# QuadADSR.net
KiCad netlist of a schematic drawn in EAGLE
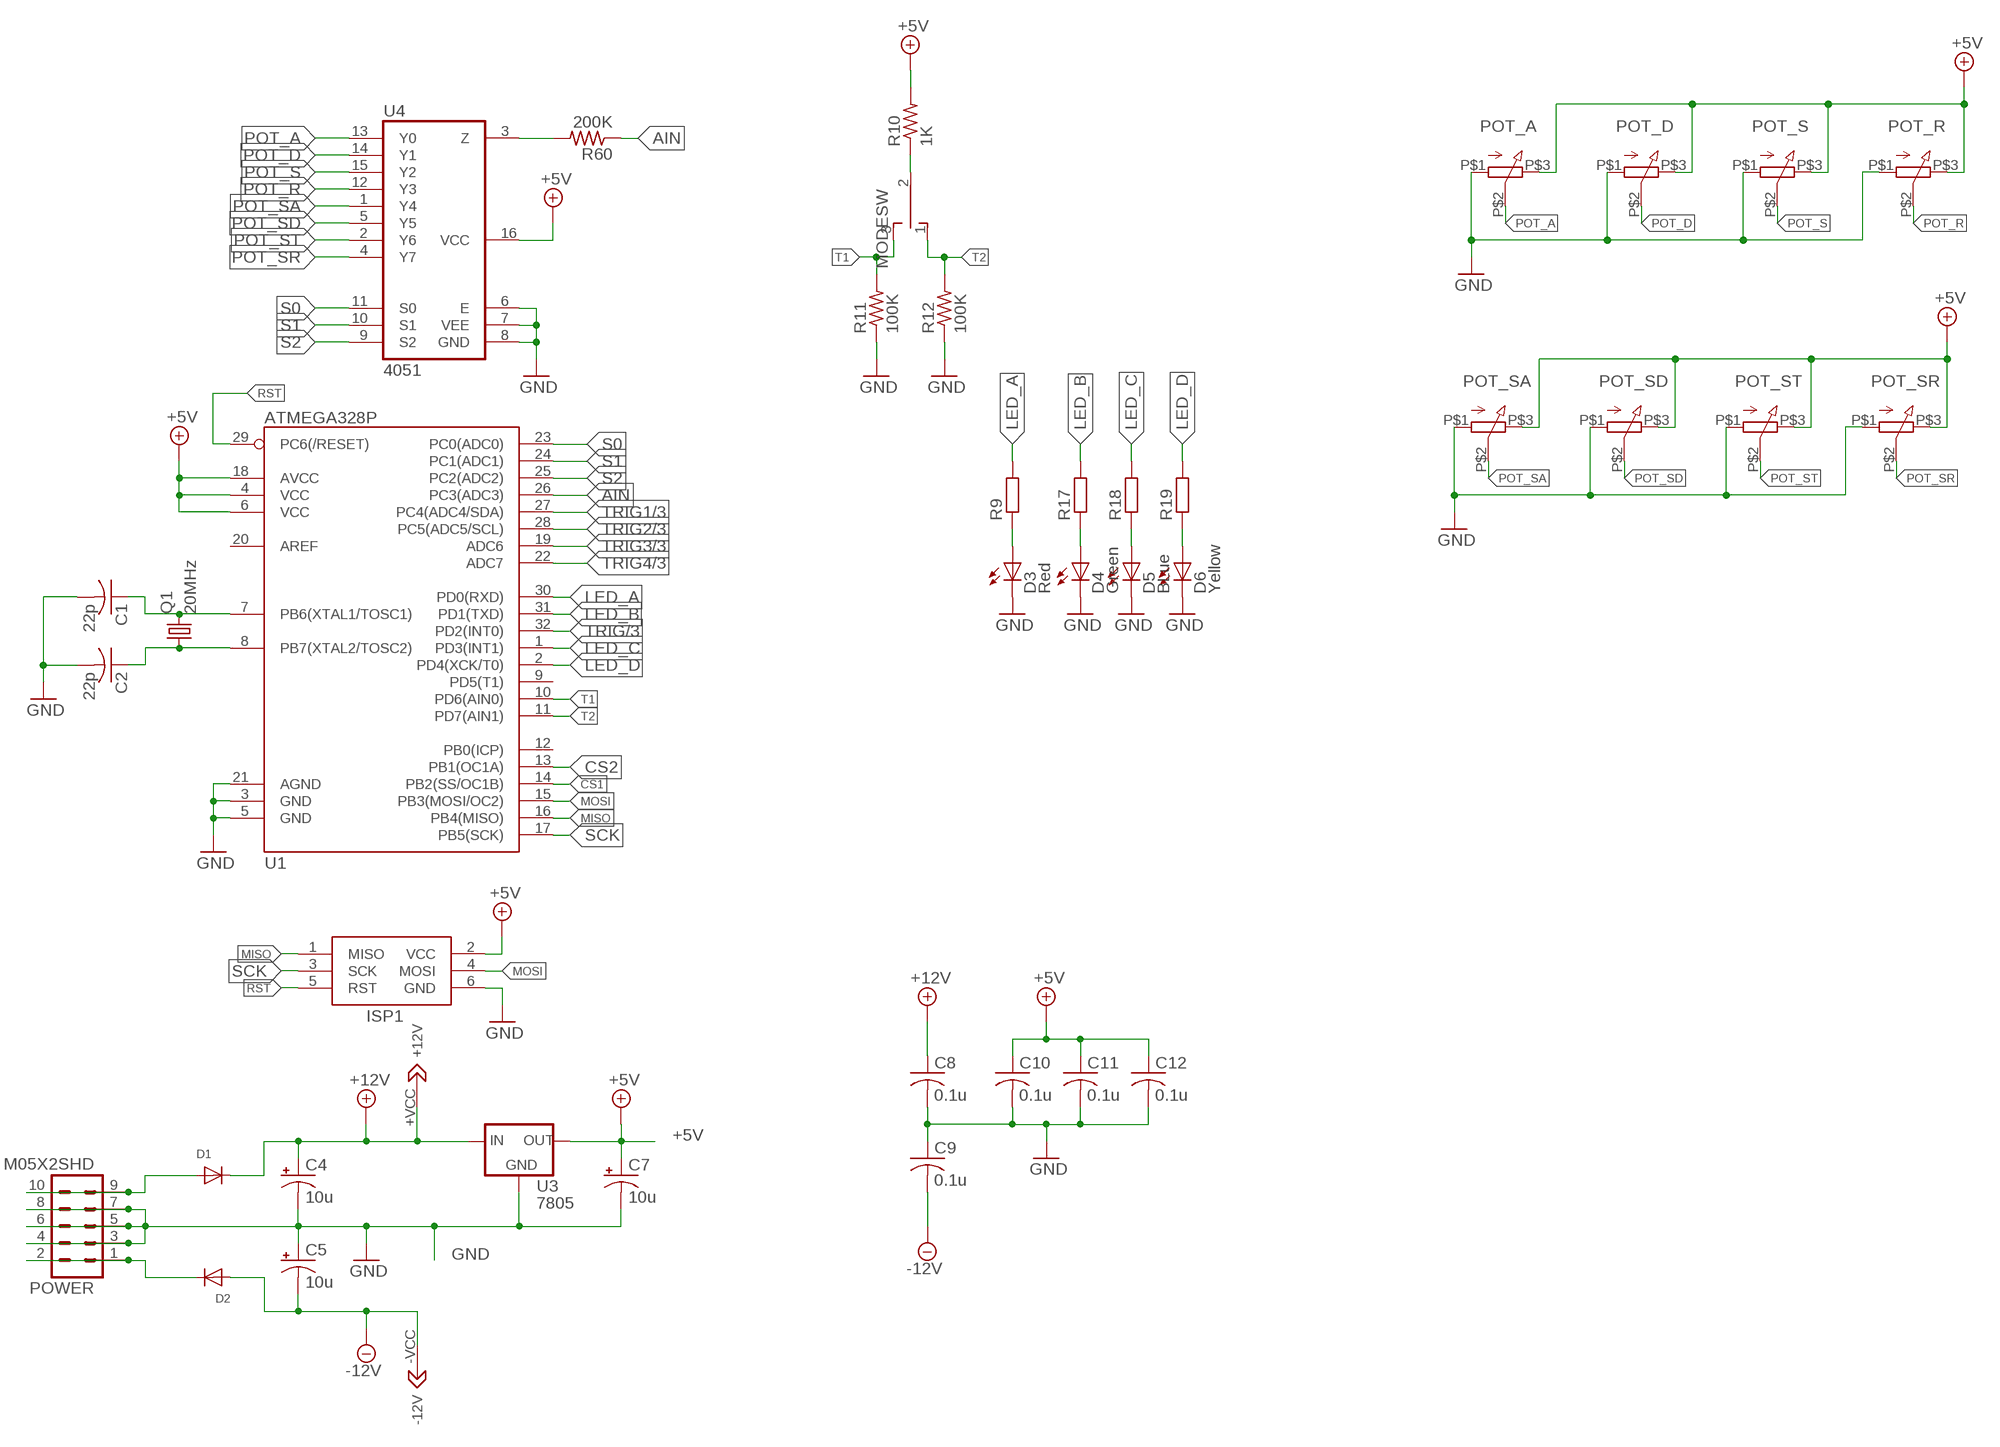
[diagram p0: schematic, sheet 1]
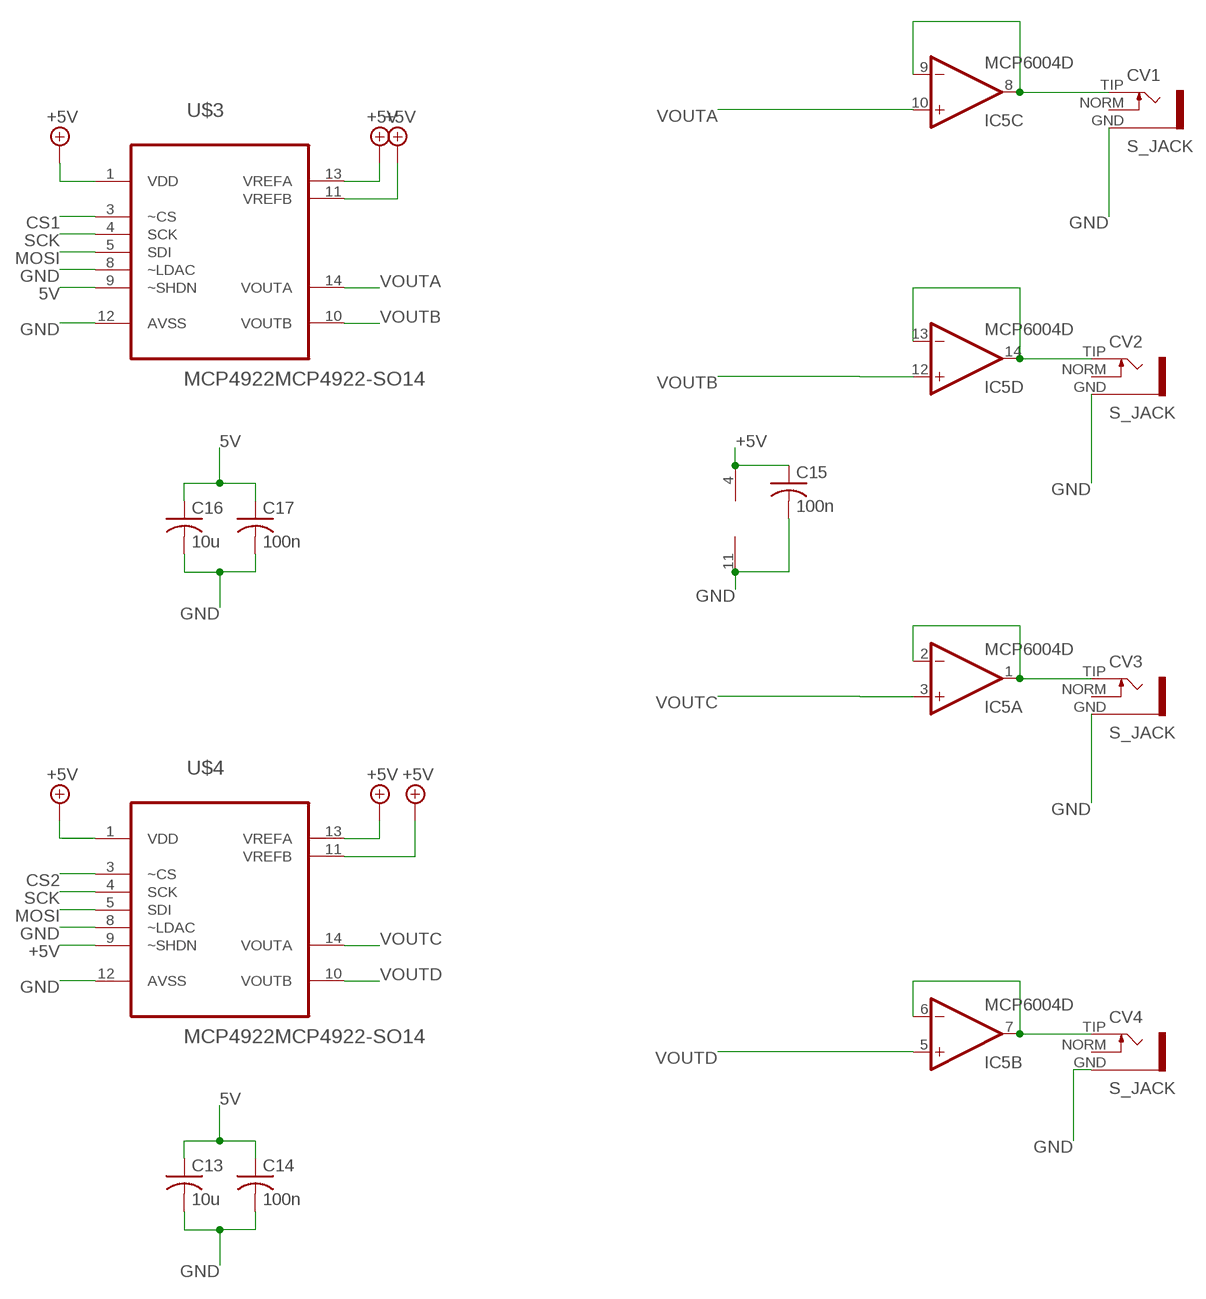
[diagram p1: schematic, sheet 2]
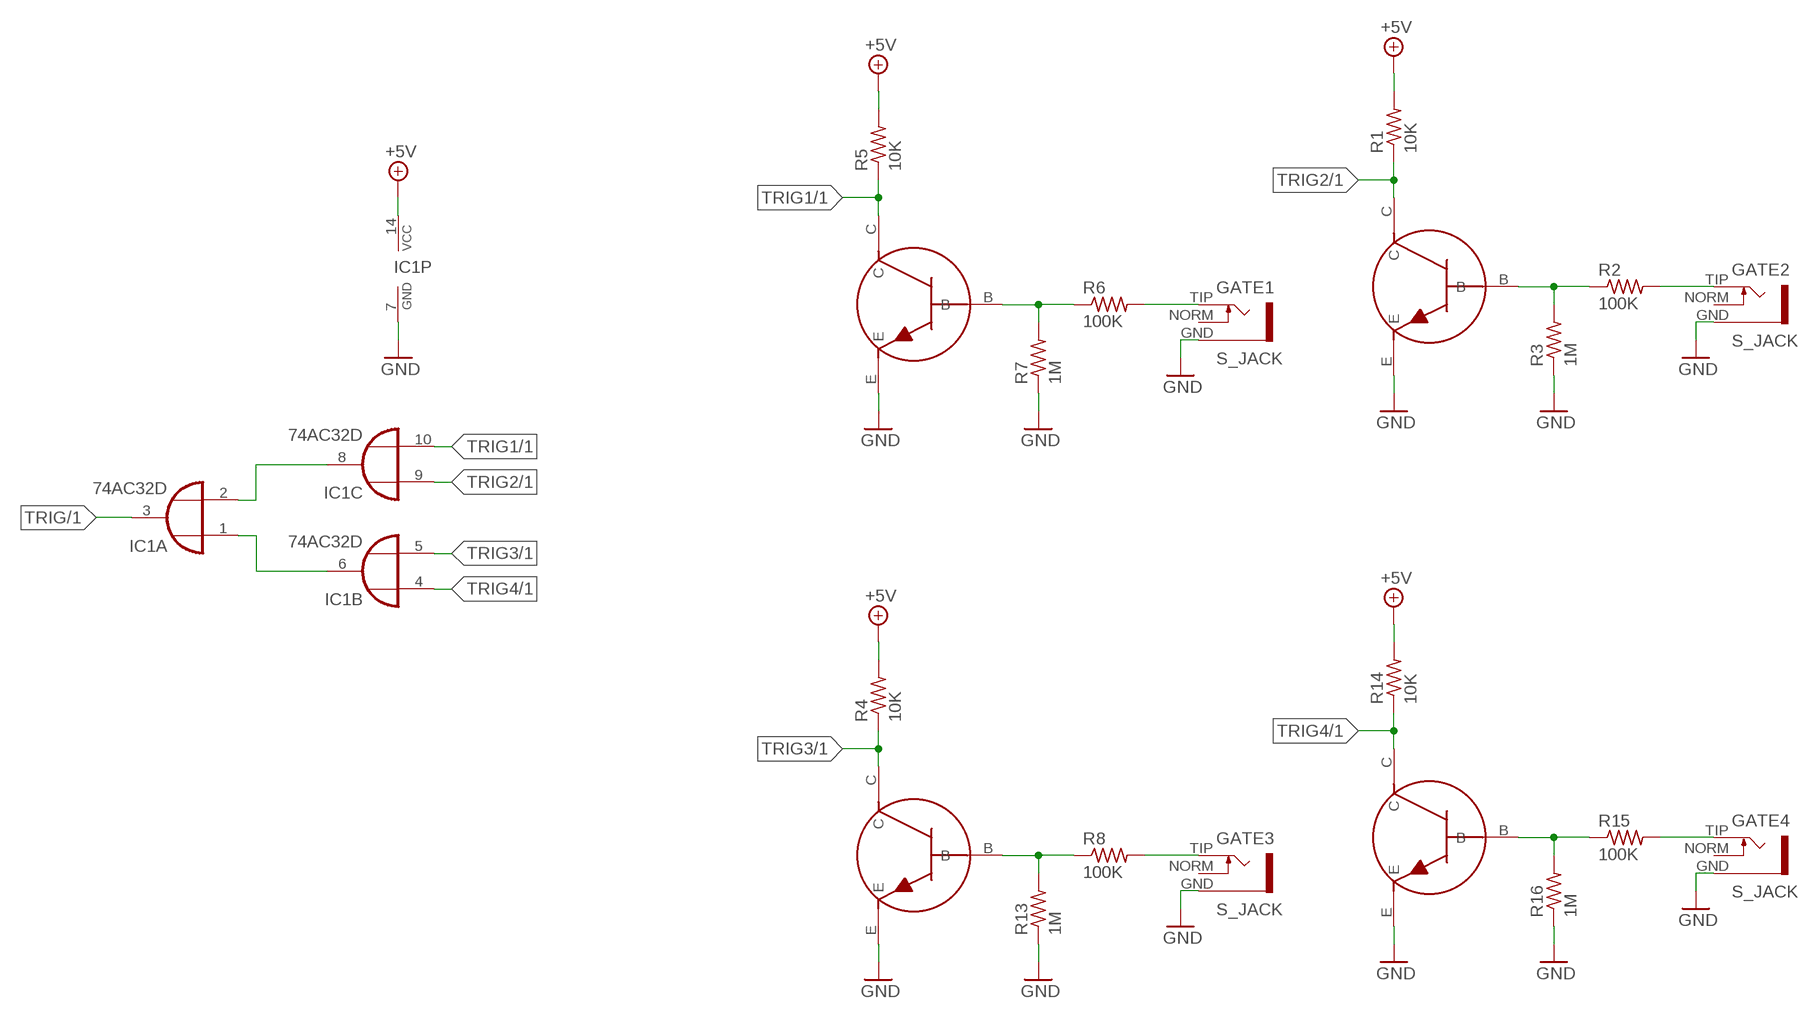
[diagram p2: schematic, sheet 3]

(export (version "E")
  (design (tool "Eeschema 10.0.6"))
  (components
    (comp (ref "C1")
      (value "22p")
      (footprint "eagle-import:C0805K")
      (libsource (lib "eagle-import") (part "C-USC0805K"))
    )
    (comp (ref "C2")
      (value "22p")
      (footprint "eagle-import:C0805K")
      (libsource (lib "eagle-import") (part "C-USC0805K"))
    )
    (comp (ref "C4")
      (value "10u")
      (footprint "eagle-import:153CLV-0505")
      (libsource (lib "eagle-import") (part "CPOL-US153CLV-0505"))
    )
    (comp (ref "C5")
      (value "10u")
      (footprint "eagle-import:153CLV-0505")
      (libsource (lib "eagle-import") (part "CPOL-US153CLV-0505"))
    )
    (comp (ref "C7")
      (value "10u")
      (footprint "eagle-import:153CLV-0505")
      (libsource (lib "eagle-import") (part "CPOL-US153CLV-0505"))
    )
    (comp (ref "C8")
      (value "0.1u")
      (footprint "eagle-import:C0805K")
      (libsource (lib "eagle-import") (part "C-USC0805K"))
    )
    (comp (ref "C9")
      (value "0.1u")
      (footprint "eagle-import:C0805K")
      (libsource (lib "eagle-import") (part "C-USC0805K"))
    )
    (comp (ref "C10")
      (value "0.1u")
      (footprint "eagle-import:C0805K")
      (libsource (lib "eagle-import") (part "C-USC0805K"))
    )
    (comp (ref "C11")
      (value "0.1u")
      (footprint "eagle-import:C0805K")
      (libsource (lib "eagle-import") (part "C-USC0805K"))
    )
    (comp (ref "C12")
      (value "0.1u")
      (footprint "eagle-import:C0805K")
      (libsource (lib "eagle-import") (part "C-USC0805K"))
    )
    (comp (ref "D1")
      (value "DIODESMA")
      (footprint "eagle-import:SMADIODE")
      (libsource (lib "eagle-import") (part "DIODESMA"))
    )
    (comp (ref "D2")
      (value "DIODESMA")
      (footprint "eagle-import:SMADIODE")
      (libsource (lib "eagle-import") (part "DIODESMA"))
    )
    (comp (ref "D3")
      (value "Red")
      (footprint "eagle-import:LED5MM")
      (libsource (lib "eagle-import") (part "LED5MM"))
    )
    (comp (ref "D4")
      (value "Green")
      (footprint "eagle-import:LED5MM")
      (libsource (lib "eagle-import") (part "LED5MM"))
    )
    (comp (ref "D5")
      (value "BLue")
      (footprint "eagle-import:LED5MM")
      (libsource (lib "eagle-import") (part "LED5MM"))
    )
    (comp (ref "D6")
      (value "Yellow")
      (footprint "eagle-import:LED5MM")
      (libsource (lib "eagle-import") (part "LED5MM"))
    )
    (comp (ref "ISP1")
      (value "AVRISP-6")
      (footprint "eagle-import:AVRISP")
      (libsource (lib "eagle-import") (part "AVRISP-6"))
    )
    (comp (ref "MODESW")
      (value "TOGGLE_ON_OFF_ON")
      (footprint "eagle-import:TOGGLE_ON_OFF_ON")
      (libsource (lib "eagle-import") (part "TOGGLE_ON_OFF_ON"))
    )
    (comp (ref "POT_A")
      (value "Q-POT")
      (footprint "eagle-import:Q-POT")
      (libsource (lib "eagle-import") (part "Q-POT"))
    )
    (comp (ref "POT_D")
      (value "Q-POT")
      (footprint "eagle-import:Q-POT")
      (libsource (lib "eagle-import") (part "Q-POT"))
    )
    (comp (ref "POT_R")
      (value "Q-POT")
      (footprint "eagle-import:Q-POT")
      (libsource (lib "eagle-import") (part "Q-POT"))
    )
    (comp (ref "POT_S")
      (value "Q-POT")
      (footprint "eagle-import:Q-POT")
      (libsource (lib "eagle-import") (part "Q-POT"))
    )
    (comp (ref "POT_SA")
      (value "Q-POT")
      (footprint "eagle-import:Q-POT")
      (libsource (lib "eagle-import") (part "Q-POT"))
    )
    (comp (ref "POT_SD")
      (value "Q-POT")
      (footprint "eagle-import:Q-POT")
      (libsource (lib "eagle-import") (part "Q-POT"))
    )
    (comp (ref "POT_SR")
      (value "Q-POT")
      (footprint "eagle-import:Q-POT")
      (libsource (lib "eagle-import") (part "Q-POT"))
    )
    (comp (ref "POT_ST")
      (value "Q-POT")
      (footprint "eagle-import:Q-POT")
      (libsource (lib "eagle-import") (part "Q-POT"))
    )
    (comp (ref "POWER")
      (value "M05X2SHD")
      (footprint "eagle-import:2X5-SHROUDED")
      (libsource (lib "eagle-import") (part "M05X2SHD"))
    )
    (comp (ref "Q1")
      (value "20MHz")
      (footprint "eagle-import:HC49UP")
      (libsource (lib "eagle-import") (part "CRYSTALHC49UP"))
    )
    (comp (ref "R9")
      (value "R-EU_R0805")
      (footprint "eagle-import:R0805")
      (libsource (lib "eagle-import") (part "R-EU_R0805"))
    )
    (comp (ref "R10")
      (value "1K")
      (footprint "eagle-import:R0805")
      (libsource (lib "eagle-import") (part "rcl_334_R-US_R0805"))
    )
    (comp (ref "R11")
      (value "100K")
      (footprint "eagle-import:R0805")
      (libsource (lib "eagle-import") (part "rcl_334_R-US_R0805"))
    )
    (comp (ref "R12")
      (value "100K")
      (footprint "eagle-import:R0805")
      (libsource (lib "eagle-import") (part "rcl_334_R-US_R0805"))
    )
    (comp (ref "R17")
      (value "R-EU_R0805")
      (footprint "eagle-import:R0805")
      (libsource (lib "eagle-import") (part "R-EU_R0805"))
    )
    (comp (ref "R18")
      (value "R-EU_R0805")
      (footprint "eagle-import:R0805")
      (libsource (lib "eagle-import") (part "R-EU_R0805"))
    )
    (comp (ref "R19")
      (value "R-EU_R0805")
      (footprint "eagle-import:R0805")
      (libsource (lib "eagle-import") (part "R-EU_R0805"))
    )
    (comp (ref "R60")
      (value "200K")
      (footprint "eagle-import:R0805")
      (libsource (lib "eagle-import") (part "R-US_R0805"))
    )
    (comp (ref "U1")
      (value "ATMEGA328P")
      (footprint "eagle-import:TQFP32-08")
      (libsource (lib "eagle-import") (part "ATMEGA328_SMT"))
    )
    (comp (ref "U2")
      (value "DUAL_OPAMP")
      (footprint "eagle-import:DUAL_OPAMP")
      (libsource (lib "eagle-import") (part "DUAL_OPAMP"))
    )
    (comp (ref "U3")
      (value "7805")
      (footprint "eagle-import:V-REG")
      (libsource (lib "eagle-import") (part "V-REG"))
    )
    (comp (ref "U4")
      (value "4051")
      (footprint "eagle-import:N2222_ARRAY")
      (libsource (lib "eagle-import") (part "MUX!"))
    )
    (comp (ref "GATE1")
      (value "S_JACK")
      (footprint "eagle-import:S_JACK")
      (libsource (lib "eagle-import") (part "S_JACK"))
    )
    (comp (ref "GATE2")
      (value "S_JACK")
      (footprint "eagle-import:S_JACK")
      (libsource (lib "eagle-import") (part "S_JACK"))
    )
    (comp (ref "GATE3")
      (value "S_JACK")
      (footprint "eagle-import:S_JACK")
      (libsource (lib "eagle-import") (part "S_JACK"))
    )
    (comp (ref "GATE4")
      (value "S_JACK")
      (footprint "eagle-import:S_JACK")
      (libsource (lib "eagle-import") (part "S_JACK"))
    )
    (comp (ref "IC1")
      (value "74AC32D")
      (footprint "eagle-import:SO14")
      (libsource (lib "eagle-import") (part "7432DAC"))
    )
    (comp (ref "R1")
      (value "10K")
      (footprint "eagle-import:R0805")
      (libsource (lib "eagle-import") (part "rcl_334_R-US_R0805"))
    )
    (comp (ref "R2")
      (value "100K")
      (footprint "eagle-import:R0805")
      (libsource (lib "eagle-import") (part "rcl_334_R-US_R0805"))
    )
    (comp (ref "R3")
      (value "1M")
      (footprint "eagle-import:R0805")
      (libsource (lib "eagle-import") (part "rcl_334_R-US_R0805"))
    )
    (comp (ref "R4")
      (value "10K")
      (footprint "eagle-import:R0805")
      (libsource (lib "eagle-import") (part "rcl_334_R-US_R0805"))
    )
    (comp (ref "R5")
      (value "10K")
      (footprint "eagle-import:R0805")
      (libsource (lib "eagle-import") (part "rcl_334_R-US_R0805"))
    )
    (comp (ref "R6")
      (value "100K")
      (footprint "eagle-import:R0805")
      (libsource (lib "eagle-import") (part "rcl_334_R-US_R0805"))
    )
    (comp (ref "R7")
      (value "1M")
      (footprint "eagle-import:R0805")
      (libsource (lib "eagle-import") (part "rcl_334_R-US_R0805"))
    )
    (comp (ref "R8")
      (value "100K")
      (footprint "eagle-import:R0805")
      (libsource (lib "eagle-import") (part "rcl_334_R-US_R0805"))
    )
    (comp (ref "R13")
      (value "1M")
      (footprint "eagle-import:R0805")
      (libsource (lib "eagle-import") (part "rcl_334_R-US_R0805"))
    )
    (comp (ref "R14")
      (value "10K")
      (footprint "eagle-import:R0805")
      (libsource (lib "eagle-import") (part "rcl_334_R-US_R0805"))
    )
    (comp (ref "R15")
      (value "100K")
      (footprint "eagle-import:R0805")
      (libsource (lib "eagle-import") (part "rcl_334_R-US_R0805"))
    )
    (comp (ref "R16")
      (value "1M")
      (footprint "eagle-import:R0805")
      (libsource (lib "eagle-import") (part "rcl_334_R-US_R0805"))
    )
    (comp (ref "T1")
      (value "2N3904")
      (footprint "eagle-import:TRANSISTOR_SINGLE_N-TYPE")
      (libsource (lib "eagle-import") (part "TRANSISTOR_MMBT3904"))
    )
    (comp (ref "T2")
      (value "2N3904")
      (footprint "eagle-import:TRANSISTOR_SINGLE_N-TYPE")
      (libsource (lib "eagle-import") (part "TRANSISTOR_MMBT3904"))
    )
    (comp (ref "T3")
      (value "2N3904")
      (footprint "eagle-import:TRANSISTOR_SINGLE_N-TYPE")
      (libsource (lib "eagle-import") (part "TRANSISTOR_MMBT3904"))
    )
    (comp (ref "T4")
      (value "2N3904")
      (footprint "eagle-import:TRANSISTOR_SINGLE_N-TYPE")
      (libsource (lib "eagle-import") (part "TRANSISTOR_MMBT3904"))
    )
    (comp (ref "C13")
      (value "10u")
      (footprint "eagle-import:C0805K")
      (libsource (lib "eagle-import") (part "C-USC0805K"))
    )
    (comp (ref "C14")
      (value "100n")
      (footprint "eagle-import:C0805K")
      (libsource (lib "eagle-import") (part "C-USC0805K"))
    )
    (comp (ref "C15")
      (value "100n")
      (footprint "eagle-import:C0805K")
      (libsource (lib "eagle-import") (part "C-USC0805K"))
    )
    (comp (ref "C16")
      (value "10u")
      (footprint "eagle-import:C0805K")
      (libsource (lib "eagle-import") (part "C-USC0805K"))
    )
    (comp (ref "C17")
      (value "100n")
      (footprint "eagle-import:C0805K")
      (libsource (lib "eagle-import") (part "C-USC0805K"))
    )
    (comp (ref "CV1")
      (value "S_JACK")
      (footprint "eagle-import:S_JACK")
      (libsource (lib "eagle-import") (part "S_JACK"))
    )
    (comp (ref "CV2")
      (value "S_JACK")
      (footprint "eagle-import:S_JACK")
      (libsource (lib "eagle-import") (part "S_JACK"))
    )
    (comp (ref "CV3")
      (value "S_JACK")
      (footprint "eagle-import:S_JACK")
      (libsource (lib "eagle-import") (part "S_JACK"))
    )
    (comp (ref "CV4")
      (value "S_JACK")
      (footprint "eagle-import:S_JACK")
      (libsource (lib "eagle-import") (part "S_JACK"))
    )
    (comp (ref "IC5")
      (value "MCP6004D")
      (footprint "eagle-import:SO14")
      (libsource (lib "eagle-import") (part "MCP6004D"))
    )
    (comp (ref "U$3")
      (value "MCP4922MCP4922-SO14")
      (footprint "eagle-import:SO14")
      (libsource (lib "eagle-import") (part "MCP4922MCP4922-SO14"))
    )
    (comp (ref "U$4")
      (value "MCP4922MCP4922-SO14")
      (footprint "eagle-import:SO14")
      (libsource (lib "eagle-import") (part "MCP4922MCP4922-SO14"))
    )
  )
  (nets
    (net (code "1") (name "+5V") (class "Default")
      (node (ref "C10") (pin "1") (pinfunction "1_1") (pintype "passive"))
      (node (ref "C11") (pin "1") (pinfunction "1_1") (pintype "passive"))
      (node (ref "C12") (pin "1") (pinfunction "1_1") (pintype "passive"))
      (node (ref "C15") (pin "1") (pinfunction "1_1") (pintype "passive"))
      (node (ref "C7") (pin "+") (pinfunction "+_+") (pintype "passive"))
      (node (ref "IC1") (pin "14") (pinfunction "VCC_14") (pintype "power_in"))
      (node (ref "IC5") (pin "4") (pinfunction "V+_4") (pintype "power_in"))
      (node (ref "ISP1") (pin "2") (pinfunction "VCC_2") (pintype "power_in"))
      (node (ref "POT_A") (pin "P$3") (pinfunction "3_P$3") (pintype "passive"))
      (node (ref "POT_D") (pin "P$3") (pinfunction "3_P$3") (pintype "passive"))
      (node (ref "POT_R") (pin "P$3") (pinfunction "3_P$3") (pintype "passive"))
      (node (ref "POT_S") (pin "P$3") (pinfunction "3_P$3") (pintype "passive"))
      (node (ref "POT_SA") (pin "P$3") (pinfunction "3_P$3") (pintype "passive"))
      (node (ref "POT_SD") (pin "P$3") (pinfunction "3_P$3") (pintype "passive"))
      (node (ref "POT_SR") (pin "P$3") (pinfunction "3_P$3") (pintype "passive"))
      (node (ref "POT_ST") (pin "P$3") (pinfunction "3_P$3") (pintype "passive"))
      (node (ref "R1") (pin "2") (pinfunction "2_2") (pintype "passive"))
      (node (ref "R10") (pin "2") (pinfunction "2_2") (pintype "passive"))
      (node (ref "R14") (pin "2") (pinfunction "2_2") (pintype "passive"))
      (node (ref "R4") (pin "2") (pinfunction "2_2") (pintype "passive"))
      (node (ref "R5") (pin "2") (pinfunction "2_2") (pintype "passive"))
      (node (ref "U$3") (pin "1") (pinfunction "VDD_1") (pintype "power_in"))
      (node (ref "U$3") (pin "11") (pinfunction "VREFB_11") (pintype "bidirectional"))
      (node (ref "U$3") (pin "13") (pinfunction "VREFA_13") (pintype "input"))
      (node (ref "U$4") (pin "1") (pinfunction "VDD_1") (pintype "power_in"))
      (node (ref "U$4") (pin "11") (pinfunction "VREFB_11") (pintype "bidirectional"))
      (node (ref "U$4") (pin "13") (pinfunction "VREFA_13") (pintype "input"))
      (node (ref "U$4") (pin "9") (pinfunction "~{SHDN}_9") (pintype "bidirectional"))
      (node (ref "U1") (pin "18") (pinfunction "AVCC_18") (pintype "bidirectional"))
      (node (ref "U1") (pin "4") (pinfunction "VCC_4") (pintype "bidirectional"))
      (node (ref "U1") (pin "6") (pinfunction "VCC_6") (pintype "bidirectional"))
      (node (ref "U3") (pin "3") (pinfunction "OUT_3") (pintype "passive"))
      (node (ref "U4") (pin "16") (pinfunction "VCC_16") (pintype "input"))
    )
    (net (code "2") (name "+12V") (class "Default")
      (node (ref "C4") (pin "+") (pinfunction "+_+") (pintype "passive"))
      (node (ref "C8") (pin "1") (pinfunction "1_1") (pintype "passive"))
      (node (ref "D1") (pin "C") (pinfunction "C_C") (pintype "passive"))
      (node (ref "U2") (pin "+VCC") (pinfunction "+12V_+VCC") (pintype "bidirectional"))
      (node (ref "U3") (pin "1") (pinfunction "IN_1") (pintype "input"))
    )
    (net (code "3") (name "-12V") (class "Default")
      (node (ref "C5") (pin "-") (pinfunction "-_-") (pintype "passive"))
      (node (ref "C9") (pin "2") (pinfunction "2_2") (pintype "passive"))
      (node (ref "D2") (pin "A") (pinfunction "A_A") (pintype "passive"))
      (node (ref "U2") (pin "-VCC") (pinfunction "-12V_-VCC") (pintype "bidirectional"))
    )
    (net (code "4") (name "5V") (class "Default")
      (node (ref "C13") (pin "1") (pinfunction "1_1") (pintype "passive"))
      (node (ref "C14") (pin "1") (pinfunction "1_1") (pintype "passive"))
      (node (ref "C16") (pin "1") (pinfunction "1_1") (pintype "passive"))
      (node (ref "C17") (pin "1") (pinfunction "1_1") (pintype "passive"))
      (node (ref "U$3") (pin "9") (pinfunction "~{SHDN}_9") (pintype "bidirectional"))
    )
    (net (code "5") (name "AIN") (class "Default")
      (node (ref "R60") (pin "1") (pinfunction "1_1") (pintype "passive"))
      (node (ref "U1") (pin "26") (pinfunction "PC3(ADC3)_26") (pintype "bidirectional"))
    )
    (net (code "6") (name "CS1") (class "Default")
      (node (ref "U$3") (pin "3") (pinfunction "~{CS}_3") (pintype "input"))
      (node (ref "U1") (pin "14") (pinfunction "PB2(SS/OC1B)_14") (pintype "bidirectional"))
    )
    (net (code "7") (name "CS2") (class "Default")
      (node (ref "U$4") (pin "3") (pinfunction "~{CS}_3") (pintype "input"))
      (node (ref "U1") (pin "13") (pinfunction "PB1(OC1A)_13") (pintype "bidirectional"))
    )
    (net (code "8") (name "GND") (class "Default")
      (node (ref "C1") (pin "2") (pinfunction "2_2") (pintype "passive"))
      (node (ref "C10") (pin "2") (pinfunction "2_2") (pintype "passive"))
      (node (ref "C11") (pin "2") (pinfunction "2_2") (pintype "passive"))
      (node (ref "C12") (pin "2") (pinfunction "2_2") (pintype "passive"))
      (node (ref "C13") (pin "2") (pinfunction "2_2") (pintype "passive"))
      (node (ref "C14") (pin "2") (pinfunction "2_2") (pintype "passive"))
      (node (ref "C15") (pin "2") (pinfunction "2_2") (pintype "passive"))
      (node (ref "C16") (pin "2") (pinfunction "2_2") (pintype "passive"))
      (node (ref "C17") (pin "2") (pinfunction "2_2") (pintype "passive"))
      (node (ref "C2") (pin "2") (pinfunction "2_2") (pintype "passive"))
      (node (ref "C4") (pin "-") (pinfunction "-_-") (pintype "passive"))
      (node (ref "C5") (pin "+") (pinfunction "+_+") (pintype "passive"))
      (node (ref "C7") (pin "-") (pinfunction "-_-") (pintype "passive"))
      (node (ref "C8") (pin "2") (pinfunction "2_2") (pintype "passive"))
      (node (ref "C9") (pin "1") (pinfunction "1_1") (pintype "passive"))
      (node (ref "CV1") (pin "GND") (pinfunction "GND_GND") (pintype "passive"))
      (node (ref "CV2") (pin "GND") (pinfunction "GND_GND") (pintype "passive"))
      (node (ref "CV3") (pin "GND") (pinfunction "GND_GND") (pintype "passive"))
      (node (ref "CV4") (pin "GND") (pinfunction "GND_GND") (pintype "passive"))
      (node (ref "D3") (pin "K") (pinfunction "C_K") (pintype "passive"))
      (node (ref "D4") (pin "K") (pinfunction "C_K") (pintype "passive"))
      (node (ref "D5") (pin "K") (pinfunction "C_K") (pintype "passive"))
      (node (ref "D6") (pin "K") (pinfunction "C_K") (pintype "passive"))
      (node (ref "GATE1") (pin "GND") (pinfunction "GND_GND") (pintype "passive"))
      (node (ref "GATE2") (pin "GND") (pinfunction "GND_GND") (pintype "passive"))
      (node (ref "GATE3") (pin "GND") (pinfunction "GND_GND") (pintype "passive"))
      (node (ref "GATE4") (pin "GND") (pinfunction "GND_GND") (pintype "passive"))
      (node (ref "IC1") (pin "7") (pinfunction "GND_7") (pintype "power_in"))
      (node (ref "IC5") (pin "11") (pinfunction "V-_11") (pintype "power_in"))
      (node (ref "ISP1") (pin "6") (pinfunction "GND_6") (pintype "power_in"))
      (node (ref "POT_A") (pin "P$1") (pinfunction "1_P$1") (pintype "passive"))
      (node (ref "POT_D") (pin "P$1") (pinfunction "1_P$1") (pintype "passive"))
      (node (ref "POT_R") (pin "P$1") (pinfunction "1_P$1") (pintype "passive"))
      (node (ref "POT_S") (pin "P$1") (pinfunction "1_P$1") (pintype "passive"))
      (node (ref "POT_SA") (pin "P$1") (pinfunction "1_P$1") (pintype "passive"))
      (node (ref "POT_SD") (pin "P$1") (pinfunction "1_P$1") (pintype "passive"))
      (node (ref "POT_SR") (pin "P$1") (pinfunction "1_P$1") (pintype "passive"))
      (node (ref "POT_ST") (pin "P$1") (pinfunction "1_P$1") (pintype "passive"))
      (node (ref "POWER") (pin "3") (pinfunction "3_3") (pintype "passive"))
      (node (ref "POWER") (pin "4") (pinfunction "4_4") (pintype "passive"))
      (node (ref "POWER") (pin "5") (pinfunction "5_5") (pintype "passive"))
      (node (ref "POWER") (pin "6") (pinfunction "6_6") (pintype "passive"))
      (node (ref "POWER") (pin "7") (pinfunction "7_7") (pintype "passive"))
      (node (ref "POWER") (pin "8") (pinfunction "8_8") (pintype "passive"))
      (node (ref "R11") (pin "1") (pinfunction "1_1") (pintype "passive"))
      (node (ref "R12") (pin "1") (pinfunction "1_1") (pintype "passive"))
      (node (ref "R13") (pin "1") (pinfunction "1_1") (pintype "passive"))
      (node (ref "R16") (pin "1") (pinfunction "1_1") (pintype "passive"))
      (node (ref "R3") (pin "1") (pinfunction "1_1") (pintype "passive"))
      (node (ref "R7") (pin "1") (pinfunction "1_1") (pintype "passive"))
      (node (ref "T1") (pin "E") (pinfunction "E_E") (pintype "bidirectional"))
      (node (ref "T2") (pin "E") (pinfunction "E_E") (pintype "bidirectional"))
      (node (ref "T3") (pin "E") (pinfunction "E_E") (pintype "bidirectional"))
      (node (ref "T4") (pin "E") (pinfunction "E_E") (pintype "bidirectional"))
      (node (ref "U$3") (pin "12") (pinfunction "AVSS_12") (pintype "passive"))
      (node (ref "U$3") (pin "8") (pinfunction "~{LDAC}_8") (pintype "input"))
      (node (ref "U$4") (pin "12") (pinfunction "AVSS_12") (pintype "passive"))
      (node (ref "U$4") (pin "8") (pinfunction "~{LDAC}_8") (pintype "input"))
      (node (ref "U1") (pin "21") (pinfunction "AGND_21") (pintype "bidirectional"))
      (node (ref "U1") (pin "3") (pinfunction "GND_3") (pintype "bidirectional"))
      (node (ref "U1") (pin "5") (pinfunction "GND_5") (pintype "bidirectional"))
      (node (ref "U3") (pin "4") (pinfunction "GND_4") (pintype "input"))
      (node (ref "U4") (pin "6") (pinfunction "E_6") (pintype "bidirectional"))
      (node (ref "U4") (pin "7") (pinfunction "VEE_7") (pintype "bidirectional"))
      (node (ref "U4") (pin "8") (pinfunction "GND_8") (pintype "bidirectional"))
    )
    (net (code "9") (name "LED_A") (class "Default")
      (node (ref "R9") (pin "2") (pinfunction "2_2") (pintype "passive"))
      (node (ref "U1") (pin "30") (pinfunction "PD0(RXD)_30") (pintype "bidirectional"))
    )
    (net (code "10") (name "LED_B") (class "Default")
      (node (ref "R17") (pin "2") (pinfunction "2_2") (pintype "passive"))
      (node (ref "U1") (pin "31") (pinfunction "PD1(TXD)_31") (pintype "bidirectional"))
    )
    (net (code "11") (name "LED_C") (class "Default")
      (node (ref "R18") (pin "2") (pinfunction "2_2") (pintype "passive"))
      (node (ref "U1") (pin "1") (pinfunction "PD3(INT1)_1") (pintype "bidirectional"))
    )
    (net (code "12") (name "LED_D") (class "Default")
      (node (ref "R19") (pin "2") (pinfunction "2_2") (pintype "passive"))
      (node (ref "U1") (pin "2") (pinfunction "PD4(XCK/T0)_2") (pintype "bidirectional"))
    )
    (net (code "13") (name "MISO") (class "Default")
      (node (ref "ISP1") (pin "1") (pinfunction "MISO_1") (pintype "input"))
      (node (ref "U1") (pin "16") (pinfunction "PB4(MISO)_16") (pintype "bidirectional"))
    )
    (net (code "14") (name "MOSI") (class "Default")
      (node (ref "ISP1") (pin "4") (pinfunction "MOSI_4") (pintype "output"))
      (node (ref "U$3") (pin "5") (pinfunction "SDI_5") (pintype "input"))
      (node (ref "U$4") (pin "5") (pinfunction "SDI_5") (pintype "input"))
      (node (ref "U1") (pin "15") (pinfunction "PB3(MOSI/OC2)_15") (pintype "bidirectional"))
    )
    (net (code "15") (name "Net-(D1-PadA)") (class "Default")
      (node (ref "D1") (pin "A") (pinfunction "A_A") (pintype "passive"))
      (node (ref "POWER") (pin "10") (pinfunction "10_10") (pintype "passive"))
      (node (ref "POWER") (pin "9") (pinfunction "9_9") (pintype "passive"))
    )
    (net (code "16") (name "Net-(D2-PadC)") (class "Default")
      (node (ref "D2") (pin "C") (pinfunction "C_C") (pintype "passive"))
      (node (ref "POWER") (pin "1") (pinfunction "1_1") (pintype "passive"))
      (node (ref "POWER") (pin "2") (pinfunction "2_2") (pintype "passive"))
    )
    (net (code "17") (name "Net-(D3-PadA)") (class "Default")
      (node (ref "D3") (pin "A") (pinfunction "A_A") (pintype "passive"))
      (node (ref "R9") (pin "1") (pinfunction "1_1") (pintype "passive"))
    )
    (net (code "18") (name "Net-(D4-PadA)") (class "Default")
      (node (ref "D4") (pin "A") (pinfunction "A_A") (pintype "passive"))
      (node (ref "R17") (pin "1") (pinfunction "1_1") (pintype "passive"))
    )
    (net (code "19") (name "Net-(D5-PadA)") (class "Default")
      (node (ref "D5") (pin "A") (pinfunction "A_A") (pintype "passive"))
      (node (ref "R18") (pin "1") (pinfunction "1_1") (pintype "passive"))
    )
    (net (code "20") (name "Net-(D6-PadA)") (class "Default")
      (node (ref "D6") (pin "A") (pinfunction "A_A") (pintype "passive"))
      (node (ref "R19") (pin "1") (pinfunction "1_1") (pintype "passive"))
    )
    (net (code "21") (name "Net-(GATE1-PadTIP)") (class "Default")
      (node (ref "GATE1") (pin "TIP") (pinfunction "TIP_TIP") (pintype "passive"))
      (node (ref "R6") (pin "2") (pinfunction "2_2") (pintype "passive"))
    )
    (net (code "22") (name "Net-(GATE2-PadTIP)") (class "Default")
      (node (ref "GATE2") (pin "TIP") (pinfunction "TIP_TIP") (pintype "passive"))
      (node (ref "R2") (pin "2") (pinfunction "2_2") (pintype "passive"))
    )
    (net (code "23") (name "Net-(GATE3-PadTIP)") (class "Default")
      (node (ref "GATE3") (pin "TIP") (pinfunction "TIP_TIP") (pintype "passive"))
      (node (ref "R8") (pin "2") (pinfunction "2_2") (pintype "passive"))
    )
    (net (code "24") (name "Net-(GATE4-PadTIP)") (class "Default")
      (node (ref "GATE4") (pin "TIP") (pinfunction "TIP_TIP") (pintype "passive"))
      (node (ref "R15") (pin "2") (pinfunction "2_2") (pintype "passive"))
    )
    (net (code "25") (name "Net-(IC1A-I0)") (class "Default")
      (node (ref "IC1") (pin "1") (pinfunction "I0_1") (pintype "input"))
      (node (ref "IC1") (pin "6") (pinfunction "O_6") (pintype "output"))
    )
    (net (code "26") (name "Net-(IC1A-I1)") (class "Default")
      (node (ref "IC1") (pin "2") (pinfunction "I1_2") (pintype "input"))
      (node (ref "IC1") (pin "8") (pinfunction "O_8") (pintype "output"))
    )
    (net (code "27") (name "Net-(IC5A--IN)") (class "Default")
      (node (ref "CV3") (pin "TIP") (pinfunction "TIP_TIP") (pintype "passive"))
      (node (ref "IC5") (pin "1") (pinfunction "OUT_1") (pintype "output"))
      (node (ref "IC5") (pin "2") (pinfunction "-IN_2") (pintype "input"))
    )
    (net (code "28") (name "Net-(IC5B--IN)") (class "Default")
      (node (ref "CV4") (pin "TIP") (pinfunction "TIP_TIP") (pintype "passive"))
      (node (ref "IC5") (pin "6") (pinfunction "-IN_6") (pintype "input"))
      (node (ref "IC5") (pin "7") (pinfunction "OUT_7") (pintype "output"))
    )
    (net (code "29") (name "Net-(IC5C--IN)") (class "Default")
      (node (ref "CV1") (pin "TIP") (pinfunction "TIP_TIP") (pintype "passive"))
      (node (ref "IC5") (pin "8") (pinfunction "OUT_8") (pintype "output"))
      (node (ref "IC5") (pin "9") (pinfunction "-IN_9") (pintype "input"))
    )
    (net (code "30") (name "Net-(IC5D--IN)") (class "Default")
      (node (ref "CV2") (pin "TIP") (pinfunction "TIP_TIP") (pintype "passive"))
      (node (ref "IC5") (pin "13") (pinfunction "-IN_13") (pintype "input"))
      (node (ref "IC5") (pin "14") (pinfunction "OUT_14") (pintype "output"))
    )
    (net (code "31") (name "Net-(MODESW-P)") (class "Default")
      (node (ref "MODESW") (pin "2") (pinfunction "P_2") (pintype "passive"))
      (node (ref "R10") (pin "1") (pinfunction "1_1") (pintype "passive"))
    )
    (net (code "32") (name "Net-(R2-Pad1)") (class "Default")
      (node (ref "R2") (pin "1") (pinfunction "1_1") (pintype "passive"))
      (node (ref "R3") (pin "2") (pinfunction "2_2") (pintype "passive"))
      (node (ref "T2") (pin "B") (pinfunction "B_B") (pintype "bidirectional"))
    )
    (net (code "33") (name "Net-(R6-Pad1)") (class "Default")
      (node (ref "R6") (pin "1") (pinfunction "1_1") (pintype "passive"))
      (node (ref "R7") (pin "2") (pinfunction "2_2") (pintype "passive"))
      (node (ref "T1") (pin "B") (pinfunction "B_B") (pintype "bidirectional"))
    )
    (net (code "34") (name "Net-(R13-Pad2)") (class "Default")
      (node (ref "R13") (pin "2") (pinfunction "2_2") (pintype "passive"))
      (node (ref "R8") (pin "1") (pinfunction "1_1") (pintype "passive"))
      (node (ref "T3") (pin "B") (pinfunction "B_B") (pintype "bidirectional"))
    )
    (net (code "35") (name "Net-(R15-Pad1)") (class "Default")
      (node (ref "R15") (pin "1") (pinfunction "1_1") (pintype "passive"))
      (node (ref "R16") (pin "2") (pinfunction "2_2") (pintype "passive"))
      (node (ref "T4") (pin "B") (pinfunction "B_B") (pintype "bidirectional"))
    )
    (net (code "36") (name "Net-(U1-PB6(XTAL1{slash}TOSC1))") (class "Default")
      (node (ref "C1") (pin "1") (pinfunction "1_1") (pintype "passive"))
      (node (ref "Q1") (pin "2") (pinfunction "2_2") (pintype "passive"))
      (node (ref "U1") (pin "7") (pinfunction "PB6(XTAL1/TOSC1)_7") (pintype "bidirectional"))
    )
    (net (code "37") (name "Net-(U1-PB7(XTAL2{slash}TOSC2))") (class "Default")
      (node (ref "C2") (pin "1") (pinfunction "1_1") (pintype "passive"))
      (node (ref "Q1") (pin "1") (pinfunction "1_1") (pintype "passive"))
      (node (ref "U1") (pin "8") (pinfunction "PB7(XTAL2/TOSC2)_8") (pintype "bidirectional"))
    )
    (net (code "38") (name "Net-(U4-Z)") (class "Default")
      (node (ref "R60") (pin "2") (pinfunction "2_2") (pintype "passive"))
      (node (ref "U4") (pin "3") (pinfunction "Z_3") (pintype "bidirectional"))
    )
    (net (code "39") (name "POT_A") (class "Default")
      (node (ref "POT_A") (pin "P$2") (pinfunction "2_P$2") (pintype "passive"))
      (node (ref "U4") (pin "13") (pinfunction "Y0_13") (pintype "bidirectional"))
    )
    (net (code "40") (name "POT_D") (class "Default")
      (node (ref "POT_D") (pin "P$2") (pinfunction "2_P$2") (pintype "passive"))
      (node (ref "U4") (pin "14") (pinfunction "Y1_14") (pintype "bidirectional"))
    )
    (net (code "41") (name "POT_R") (class "Default")
      (node (ref "POT_R") (pin "P$2") (pinfunction "2_P$2") (pintype "passive"))
      (node (ref "U4") (pin "12") (pinfunction "Y3_12") (pintype "bidirectional"))
    )
    (net (code "42") (name "POT_S") (class "Default")
      (node (ref "POT_S") (pin "P$2") (pinfunction "2_P$2") (pintype "passive"))
      (node (ref "U4") (pin "15") (pinfunction "Y2_15") (pintype "bidirectional"))
    )
    (net (code "43") (name "POT_SA") (class "Default")
      (node (ref "POT_SA") (pin "P$2") (pinfunction "2_P$2") (pintype "passive"))
      (node (ref "U4") (pin "1") (pinfunction "Y4_1") (pintype "bidirectional"))
    )
    (net (code "44") (name "POT_SD") (class "Default")
      (node (ref "POT_SD") (pin "P$2") (pinfunction "2_P$2") (pintype "passive"))
      (node (ref "U4") (pin "5") (pinfunction "Y5_5") (pintype "bidirectional"))
    )
    (net (code "45") (name "POT_SR") (class "Default")
      (node (ref "POT_SR") (pin "P$2") (pinfunction "2_P$2") (pintype "passive"))
      (node (ref "U4") (pin "4") (pinfunction "Y7_4") (pintype "bidirectional"))
    )
    (net (code "46") (name "POT_ST") (class "Default")
      (node (ref "POT_ST") (pin "P$2") (pinfunction "2_P$2") (pintype "passive"))
      (node (ref "U4") (pin "2") (pinfunction "Y6_2") (pintype "bidirectional"))
    )
    (net (code "47") (name "RST") (class "Default")
      (node (ref "ISP1") (pin "5") (pinfunction "RST_5") (pintype "output"))
      (node (ref "U1") (pin "29") (pinfunction "PC6(/RESET)_29") (pintype "bidirectional"))
    )
    (net (code "48") (name "S0") (class "Default")
      (node (ref "U1") (pin "23") (pinfunction "PC0(ADC0)_23") (pintype "bidirectional"))
      (node (ref "U4") (pin "11") (pinfunction "S0_11") (pintype "input"))
    )
    (net (code "49") (name "S1") (class "Default")
      (node (ref "U1") (pin "24") (pinfunction "PC1(ADC1)_24") (pintype "bidirectional"))
      (node (ref "U4") (pin "10") (pinfunction "S1_10") (pintype "input"))
    )
    (net (code "50") (name "S2") (class "Default")
      (node (ref "U1") (pin "25") (pinfunction "PC2(ADC2)_25") (pintype "bidirectional"))
      (node (ref "U4") (pin "9") (pinfunction "S2_9") (pintype "input"))
    )
    (net (code "51") (name "SCK") (class "Default")
      (node (ref "ISP1") (pin "3") (pinfunction "SCK_3") (pintype "output"))
      (node (ref "U$3") (pin "4") (pinfunction "SCK_4") (pintype "input"))
      (node (ref "U$4") (pin "4") (pinfunction "SCK_4") (pintype "input"))
      (node (ref "U1") (pin "17") (pinfunction "PB5(SCK)_17") (pintype "bidirectional"))
    )
    (net (code "52") (name "T1") (class "Default")
      (node (ref "MODESW") (pin "3") (pinfunction "S_3") (pintype "passive"))
      (node (ref "R11") (pin "2") (pinfunction "2_2") (pintype "passive"))
      (node (ref "U1") (pin "10") (pinfunction "PD6(AIN0)_10") (pintype "bidirectional"))
    )
    (net (code "53") (name "T2") (class "Default")
      (node (ref "MODESW") (pin "1") (pinfunction "O_1") (pintype "passive"))
      (node (ref "R12") (pin "2") (pinfunction "2_2") (pintype "passive"))
      (node (ref "U1") (pin "11") (pinfunction "PD7(AIN1)_11") (pintype "bidirectional"))
    )
    (net (code "54") (name "TRIG") (class "Default")
      (node (ref "IC1") (pin "3") (pinfunction "O_3") (pintype "output"))
      (node (ref "U1") (pin "32") (pinfunction "PD2(INT0)_32") (pintype "bidirectional"))
    )
    (net (code "55") (name "TRIG1") (class "Default")
      (node (ref "IC1") (pin "10") (pinfunction "I1_10") (pintype "input"))
      (node (ref "R5") (pin "1") (pinfunction "1_1") (pintype "passive"))
      (node (ref "T1") (pin "C") (pinfunction "C_C") (pintype "bidirectional"))
      (node (ref "U1") (pin "27") (pinfunction "PC4(ADC4/SDA)_27") (pintype "bidirectional"))
    )
    (net (code "56") (name "TRIG2") (class "Default")
      (node (ref "IC1") (pin "9") (pinfunction "I0_9") (pintype "input"))
      (node (ref "R1") (pin "1") (pinfunction "1_1") (pintype "passive"))
      (node (ref "T2") (pin "C") (pinfunction "C_C") (pintype "bidirectional"))
      (node (ref "U1") (pin "28") (pinfunction "PC5(ADC5/SCL)_28") (pintype "bidirectional"))
    )
    (net (code "57") (name "TRIG3") (class "Default")
      (node (ref "IC1") (pin "5") (pinfunction "I1_5") (pintype "input"))
      (node (ref "R4") (pin "1") (pinfunction "1_1") (pintype "passive"))
      (node (ref "T3") (pin "C") (pinfunction "C_C") (pintype "bidirectional"))
      (node (ref "U1") (pin "19") (pinfunction "ADC6_19") (pintype "bidirectional"))
    )
    (net (code "58") (name "TRIG4") (class "Default")
      (node (ref "IC1") (pin "4") (pinfunction "I0_4") (pintype "input"))
      (node (ref "R14") (pin "1") (pinfunction "1_1") (pintype "passive"))
      (node (ref "T4") (pin "C") (pinfunction "C_C") (pintype "bidirectional"))
      (node (ref "U1") (pin "22") (pinfunction "ADC7_22") (pintype "bidirectional"))
    )
    (net (code "59") (name "VOUTA") (class "Default")
      (node (ref "IC5") (pin "10") (pinfunction "+IN_10") (pintype "input"))
      (node (ref "U$3") (pin "14") (pinfunction "VOUTA_14") (pintype "output"))
    )
    (net (code "60") (name "VOUTB") (class "Default")
      (node (ref "IC5") (pin "12") (pinfunction "+IN_12") (pintype "input"))
      (node (ref "U$3") (pin "10") (pinfunction "VOUTB_10") (pintype "output"))
    )
    (net (code "61") (name "VOUTC") (class "Default")
      (node (ref "IC5") (pin "3") (pinfunction "+IN_3") (pintype "input"))
      (node (ref "U$4") (pin "14") (pinfunction "VOUTA_14") (pintype "output"))
    )
    (net (code "62") (name "VOUTD") (class "Default")
      (node (ref "IC5") (pin "5") (pinfunction "+IN_5") (pintype "input"))
      (node (ref "U$4") (pin "10") (pinfunction "VOUTB_10") (pintype "output"))
    )
    (net (code "63") (name "unconnected-(CV1-PadNORM)") (class "Default")
      (node (ref "CV1") (pin "NORM") (pinfunction "NORM_NORM") (pintype "passive"))
    )
    (net (code "64") (name "unconnected-(CV2-PadNORM)") (class "Default")
      (node (ref "CV2") (pin "NORM") (pinfunction "NORM_NORM") (pintype "passive"))
    )
    (net (code "65") (name "unconnected-(CV3-PadNORM)") (class "Default")
      (node (ref "CV3") (pin "NORM") (pinfunction "NORM_NORM") (pintype "passive"))
    )
    (net (code "66") (name "unconnected-(CV4-PadNORM)") (class "Default")
      (node (ref "CV4") (pin "NORM") (pinfunction "NORM_NORM") (pintype "passive"))
    )
    (net (code "67") (name "unconnected-(GATE1-PadNORM)") (class "Default")
      (node (ref "GATE1") (pin "NORM") (pinfunction "NORM_NORM") (pintype "passive"))
    )
    (net (code "68") (name "unconnected-(GATE2-PadNORM)") (class "Default")
      (node (ref "GATE2") (pin "NORM") (pinfunction "NORM_NORM") (pintype "passive"))
    )
    (net (code "69") (name "unconnected-(GATE3-PadNORM)") (class "Default")
      (node (ref "GATE3") (pin "NORM") (pinfunction "NORM_NORM") (pintype "passive"))
    )
    (net (code "70") (name "unconnected-(GATE4-PadNORM)") (class "Default")
      (node (ref "GATE4") (pin "NORM") (pinfunction "NORM_NORM") (pintype "passive"))
    )
    (net (code "71") (name "unconnected-(U1-AREF-Pad20)") (class "Default")
      (node (ref "U1") (pin "20") (pinfunction "AREF_20") (pintype "bidirectional"))
    )
    (net (code "72") (name "unconnected-(U1-PB0(ICP)-Pad12)") (class "Default")
      (node (ref "U1") (pin "12") (pinfunction "PB0(ICP)_12") (pintype "bidirectional"))
    )
    (net (code "73") (name "unconnected-(U1-PD5(T1)-Pad9)") (class "Default")
      (node (ref "U1") (pin "9") (pinfunction "PD5(T1)_9") (pintype "bidirectional"))
    )
  )
)
